# POWER.net
KiCad netlist of a schematic drawn in Altium Designer
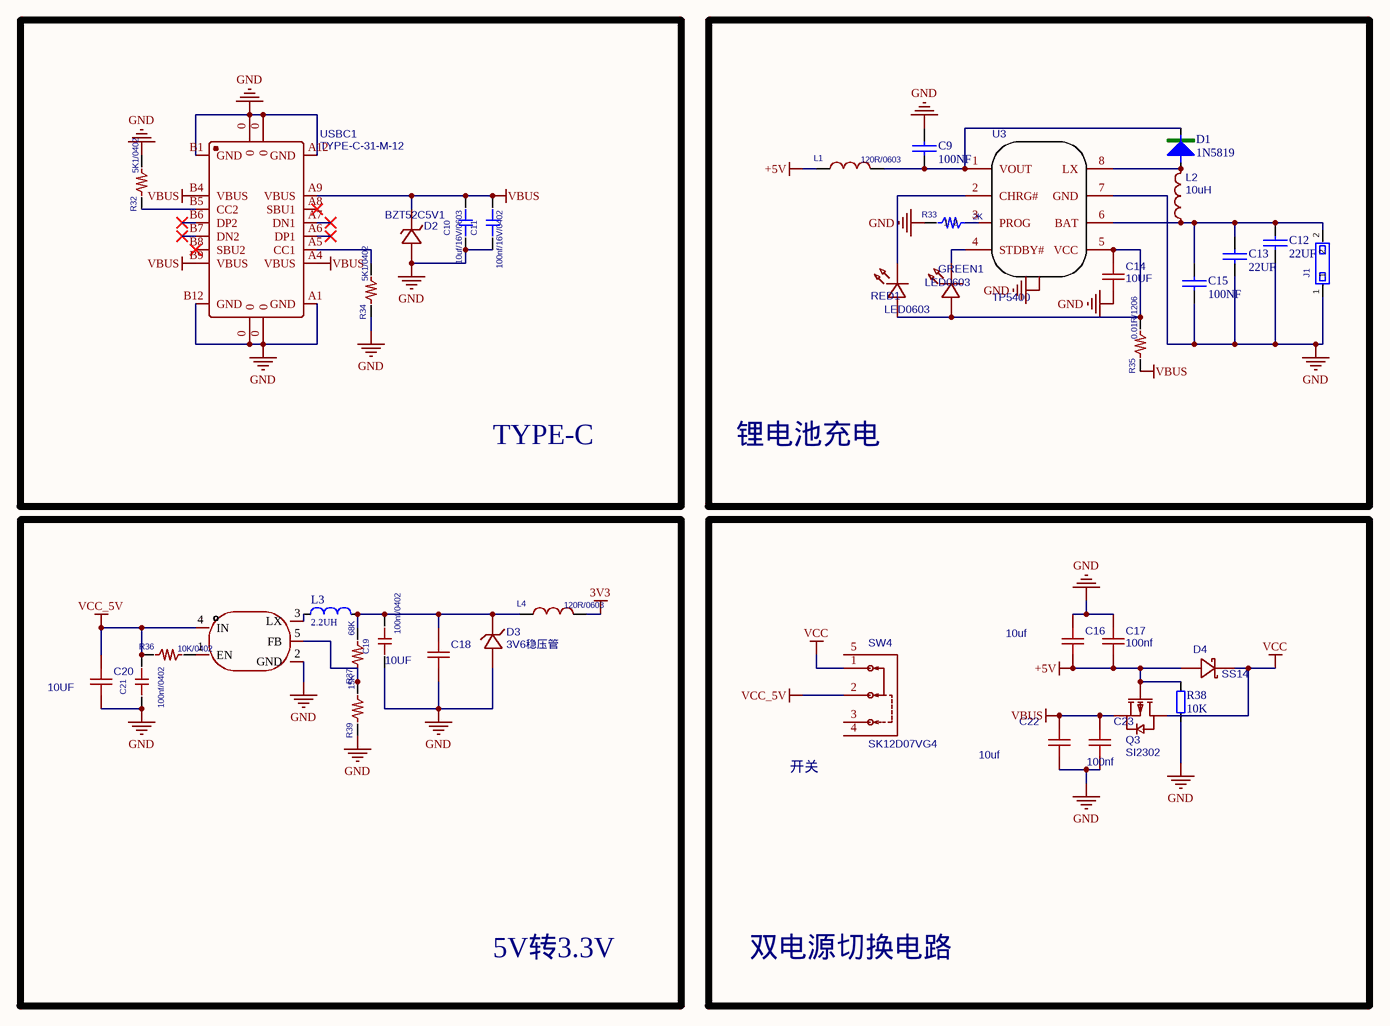
[diagram p0: POWER.SchDoc]

(export (version "E")
  (design (tool "Eeschema 10.0.6"))
  (components
    (comp (ref "C9")
      (value "100NF")
      (footprint "C0402")
      (description "Capacitor")
      (libsource (lib "mylib") (part "C0805"))
    )
    (comp (ref "C10")
      (value "10uf/16V/0603")
      (footprint "C0402")
      (fields (field (name "Comment") "100nf"))
      (libsource (lib "mylib") (part "C0402"))
    )
    (comp (ref "C11")
      (value "100nf/16V/0402")
      (footprint "C0402")
      (fields (field (name "Comment") "100nf"))
      (libsource (lib "mylib") (part "C0402"))
    )
    (comp (ref "C12")
      (value "22UF")
      (footprint "C0603")
      (description "Capacitor")
      (libsource (lib "mylib") (part "C0805"))
    )
    (comp (ref "C13")
      (value "22UF")
      (footprint "C0603")
      (description "Capacitor")
      (libsource (lib "mylib") (part "C0805"))
    )
    (comp (ref "C14")
      (value "10UF")
      (footprint "C0402")
      (fields
        (field (name "BOM_SUPPLIER PART") "C15415")
        (field (name "BOM_MANUFACTURER PART") "10uF")
        (field (name "CONTRIBUTOR") "LCSC")
      )
      (libsource (lib "mylib") (part "C0603"))
    )
    (comp (ref "C15")
      (value "100NF")
      (footprint "C0402")
      (description "Capacitor")
      (libsource (lib "mylib") (part "C0805"))
    )
    (comp (ref "C16")
      (value "10uf")
      (footprint "C0603")
      (fields
        (field (name "BOM_SUPPLIER PART") "C15415")
        (field (name "BOM_MANUFACTURER PART") "10uF")
        (field (name "CONTRIBUTOR") "LCSC")
      )
      (libsource (lib "Free Documents") (part "10uf"))
    )
    (comp (ref "C17")
      (value "100nf")
      (footprint "C0402")
      (fields
        (field (name "BOM_SUPPLIER PART") "C15415")
        (field (name "BOM_MANUFACTURER PART") "10uF")
        (field (name "CONTRIBUTOR") "LCSC")
      )
      (libsource (lib "Free Documents") (part "10uf"))
    )
    (comp (ref "C18")
      (value "10UF")
      (footprint "C0603")
      (fields
        (field (name "BOM_SUPPLIER PART") "C15415")
        (field (name "BOM_MANUFACTURER PART") "10uF")
        (field (name "CONTRIBUTOR") "LCSC")
      )
      (libsource (lib "mylib") (part "C0603"))
    )
    (comp (ref "C19")
      (value "100nf/0402")
      (footprint "C0402")
      (fields (field (name "Comment") "100nf"))
      (libsource (lib "mylib") (part "C0402"))
    )
    (comp (ref "C20")
      (value "10UF")
      (footprint "C0603")
      (fields
        (field (name "BOM_SUPPLIER PART") "C15415")
        (field (name "BOM_MANUFACTURER PART") "10uF")
        (field (name "CONTRIBUTOR") "LCSC")
      )
      (libsource (lib "mylib") (part "C0603"))
    )
    (comp (ref "C21")
      (value "100nf/0402")
      (footprint "C0402")
      (fields (field (name "Comment") "100nf"))
      (libsource (lib "mylib") (part "C0402"))
    )
    (comp (ref "C22")
      (value "10uf")
      (footprint "C0603")
      (fields
        (field (name "BOM_SUPPLIER PART") "C15415")
        (field (name "BOM_MANUFACTURER PART") "10uF")
        (field (name "CONTRIBUTOR") "LCSC")
      )
      (libsource (lib "Free Documents") (part "10uf"))
    )
    (comp (ref "C23")
      (value "100nf")
      (footprint "C0402")
      (fields
        (field (name "BOM_SUPPLIER PART") "C15415")
        (field (name "BOM_MANUFACTURER PART") "10uF")
        (field (name "CONTRIBUTOR") "LCSC")
      )
      (libsource (lib "Free Documents") (part "10uf"))
    )
    (comp (ref "D1")
      (value "1N5819")
      (footprint "SOD-123_L2.7-W1.6")
      (description "肖特基二极管")
      (libsource (lib "mylib") (part "1N5819"))
    )
    (comp (ref "D2")
      (value "BZT52C5V1")
      (footprint "SOD-123_L2.7-W1.6")
      (fields (field (name "BOM_SUPPLIER PART") "C1884555") (field (name "CONTRIBUTOR") "LCSC"))
      (libsource (lib "电源板") (part "BZT52C5V1_C1884555"))
    )
    (comp (ref "D3")
      (value "3V6稳压管")
      (footprint "SOD-123_L2.7-W1.6")
      (description "稳压管")
      (fields
        (field (name "BOM_SUPPLIER PART") "C216707")
        (field (name "BOM_MANUFACTURER PART") "BZT52C3V3")
        (field (name "CONTRIBUTOR") "LCSC")
      )
      (libsource (lib "mylib") (part "D_STB"))
    )
    (comp (ref "D4")
      (value "SS14")
      (footprint "SOD-123_L2.7-W1.6")
      (fields
        (field (name "BOM_SUPPLIER PART") "C2909963")
        (field (name "BOM_MANUFACTURER PART") "SS34")
        (field (name "CONTRIBUTOR") "LCSC")
      )
      (libsource (lib "mylib") (part "SS34_C2909963"))
    )
    (comp (ref "GREEN1")
      (value "LED0603")
      (footprint "LED0603")
      (fields
        (field (name "BOM_MANUFACTURER PART") "19-217/R6C-AL1M2VY/3T")
        (field (name "BOM_SUPPLIER PART") "C72044")
        (field (name "CONTRIBUTOR") "LCEDA_01")
      )
      (libsource (lib "mylib") (part "LED0603"))
    )
    (comp (ref "J1")
      (value "1X2PIN_SMD")
      (footprint "SMD1X2_2.54")
      (libsource (lib "mylib") (part "1X2PIN_SMD"))
    )
    (comp (ref "L1")
      (value "120R/0603")
      (footprint "L0603")
      (description "0603")
      (fields (field (name "Comment") "120R"))
      (libsource (lib "mylib") (part "FB0603"))
    )
    (comp (ref "L2")
      (value "10uH")
      (footprint "L_SMD_L4.0-W4.0")
      (fields
        (field (name "BOM_MANUFACTURER PART") "SWPA4030S100MT")
        (field (name "BOM_SUPPLIER PART") "C38117")
      )
      (libsource (lib "mylib") (part "10uH"))
    )
    (comp (ref "L3")
      (value "2.2UH")
      (footprint "L_SMD_L4.0-W4.0")
      (description "电感")
      (libsource (lib "mylib") (part "INDUCTOR"))
    )
    (comp (ref "L4")
      (value "120R/0603")
      (footprint "L0603")
      (description "0603")
      (fields (field (name "Comment") "120R"))
      (libsource (lib "mylib") (part "FB0603"))
    )
    (comp (ref "Q3")
      (value "SI2302")
      (footprint "SOT-23-3_L2.9-W1.6-P1.90")
      (description "P场效应管")
      (fields
        (field (name "BOM_SUPPLIER PART") "C518789")
        (field (name "BOM_MANUFACTURER PART") "FDN338P")
        (field (name "CONTRIBUTOR") "LCSC")
      )
      (libsource (lib "mylib") (part "FDN338P_C518789"))
    )
    (comp (ref "R32")
      (value "5K1/0402")
      (footprint "R0402")
      (fields (field (name "Comment") "5K1"))
      (libsource (lib "mylib") (part "R0402"))
    )
    (comp (ref "R33") (value "2K") (footprint "R0603") (libsource (lib "mylib") (part "R0603")))
    (comp (ref "R34")
      (value "5K1/0402")
      (footprint "R0402")
      (fields (field (name "Comment") "5K1"))
      (libsource (lib "mylib") (part "R0402"))
    )
    (comp (ref "R35")
      (value "0.01R/1206")
      (footprint "R1206")
      (fields (field (name "Comment") "0.01R"))
      (libsource (lib "mylib") (part "R1206"))
    )
    (comp (ref "R36")
      (value "10K/0402")
      (footprint "R0402")
      (fields (field (name "Comment") "R0603"))
      (libsource (lib "mylib") (part "R0402"))
    )
    (comp (ref "R37") (value "68K") (footprint "R0402") (libsource (lib "mylib") (part "R0402")))
    (comp (ref "R38") (value "10K") (footprint "R0402") (libsource (lib "") (part "R0402_1")))
    (comp (ref "R39") (value "15K") (footprint "R0402") (libsource (lib "mylib") (part "R0402")))
    (comp (ref "RED1")
      (value "LED0603")
      (footprint "LED0603")
      (fields
        (field (name "BOM_MANUFACTURER PART") "19-217/R6C-AL1M2VY/3T")
        (field (name "BOM_SUPPLIER PART") "C72044")
        (field (name "CONTRIBUTOR") "LCEDA_01")
      )
      (libsource (lib "mylib") (part "LED0603"))
    )
    (comp (ref "SW4")
      (value "SK12D07VG4")
      (footprint "SW-TH_5P")
      (description "拨动开关")
      (fields (field (name "BOM_SUPPLIER PART") "C393937") (field (name "CONTRIBUTOR") "LCSC"))
      (libsource (lib "mylib") (part "SW-bodong"))
    )
    (comp (ref "U3")
      (value "TP5400")
      (footprint "SOIC-8_L5.0-W4.0-P1.27-LS6.0_EP2.0")
      (description "锂电池充放电")
      (fields (field (name "BOM_SUPPLIER PART") "C24154"))
      (libsource (lib "mylib") (part "TP5400"))
    )
    (comp (ref "U4")
      (value "SY8088AAC")
      (footprint "SOT23-5")
      (fields (field (name "MANUFACTURER") "矽力杰silergy"))
      (libsource (lib "mylib") (part "SY8088AAC"))
    )
    (comp (ref "USBC1")
      (value "TYPE-C-31-M-12")
      (footprint "TYPEC_F_16_SMD_U")
      (fields (field (name "BOM_SUPPLIER PART") "C165948") (field (name "CONTRIBUTOR") "LCSC"))
      (libsource (lib "mylib") (part "TYPE-C-31-M-12"))
    )
  )
  (nets
    (net (code "1") (name "+5V") (class "Default")
      (node (ref "C16") (pin "2") (pinfunction "2_2") (pintype "passive"))
      (node (ref "C17") (pin "2") (pinfunction "2_2") (pintype "passive"))
      (node (ref "D4") (pin "2") (pinfunction "2_2") (pintype "passive"))
      (node (ref "L1") (pin "1") (pinfunction "1_1") (pintype "passive"))
      (node (ref "Q3") (pin "1") (pinfunction "G_1") (pintype "passive"))
      (node (ref "R38") (pin "2") (pinfunction "2_2") (pintype "passive"))
    )
    (net (code "2") (name "3V3") (class "Default")
      (node (ref "L4") (pin "2") (pinfunction "2_2") (pintype "passive"))
    )
    (net (code "3") (name "GND") (class "Default")
      (node (ref "C10") (pin "1") (pinfunction "1_1") (pintype "passive"))
      (node (ref "C11") (pin "1") (pinfunction "1_1") (pintype "passive"))
      (node (ref "C12") (pin "2") (pinfunction "2_2") (pintype "passive"))
      (node (ref "C13") (pin "2") (pinfunction "2_2") (pintype "passive"))
      (node (ref "C14") (pin "1") (pinfunction "1_1") (pintype "passive"))
      (node (ref "C15") (pin "2") (pinfunction "2_2") (pintype "passive"))
      (node (ref "C16") (pin "1") (pinfunction "1_1") (pintype "passive"))
      (node (ref "C17") (pin "1") (pinfunction "1_1") (pintype "passive"))
      (node (ref "C18") (pin "1") (pinfunction "1_1") (pintype "passive"))
      (node (ref "C19") (pin "1") (pinfunction "1_1") (pintype "passive"))
      (node (ref "C20") (pin "1") (pinfunction "1_1") (pintype "passive"))
      (node (ref "C21") (pin "1") (pinfunction "1_1") (pintype "passive"))
      (node (ref "C22") (pin "1") (pinfunction "1_1") (pintype "passive"))
      (node (ref "C23") (pin "1") (pinfunction "1_1") (pintype "passive"))
      (node (ref "C9") (pin "1") (pinfunction "1_1") (pintype "passive"))
      (node (ref "D2") (pin "2") (pinfunction "A_2") (pintype "passive"))
      (node (ref "D3") (pin "2") (pinfunction "2_2") (pintype "passive"))
      (node (ref "J1") (pin "1") (pinfunction "1_1") (pintype "passive"))
      (node (ref "R32") (pin "2") (pinfunction "2_2") (pintype "passive"))
      (node (ref "R33") (pin "1") (pinfunction "1_1") (pintype "passive"))
      (node (ref "R34") (pin "1") (pinfunction "1_1") (pintype "passive"))
      (node (ref "R38") (pin "1") (pinfunction "1_1") (pintype "passive"))
      (node (ref "R39") (pin "1") (pinfunction "1_1") (pintype "passive"))
      (node (ref "U3") (pin "7") (pinfunction "GND_7") (pintype "passive"))
      (node (ref "U3") (pin "9") (pinfunction "9_9") (pintype "passive"))
      (node (ref "U4") (pin "2") (pinfunction "GND_2") (pintype "passive"))
      (node (ref "USBC1") (pin "0") (pinfunction "0_0") (pintype "passive"))
      (node (ref "USBC1") (pin "A1") (pinfunction "GND_A1") (pintype "passive"))
      (node (ref "USBC1") (pin "A12") (pinfunction "GND_A12") (pintype "passive"))
      (node (ref "USBC1") (pin "B1") (pinfunction "GND_B1") (pintype "passive"))
      (node (ref "USBC1") (pin "B12") (pinfunction "GND_B12") (pintype "passive"))
    )
    (net (code "4") (name "Net-(C18-Pad2)") (class "Default")
      (node (ref "C18") (pin "2") (pinfunction "2_2") (pintype "passive"))
      (node (ref "C19") (pin "2") (pinfunction "2_2") (pintype "passive"))
      (node (ref "D3") (pin "1") (pinfunction "1_1") (pintype "passive"))
      (node (ref "L3") (pin "2") (pinfunction "2_2") (pintype "passive"))
      (node (ref "L4") (pin "1") (pinfunction "1_1") (pintype "passive"))
      (node (ref "R37") (pin "2") (pinfunction "2_2") (pintype "passive"))
    )
    (net (code "5") (name "Net-(U3-BAT)") (class "Default")
      (node (ref "C12") (pin "1") (pinfunction "1_1") (pintype "passive"))
      (node (ref "C13") (pin "1") (pinfunction "1_1") (pintype "passive"))
      (node (ref "C15") (pin "1") (pinfunction "1_1") (pintype "passive"))
      (node (ref "J1") (pin "2") (pinfunction "2_2") (pintype "passive"))
      (node (ref "L2") (pin "1") (pinfunction "1_1") (pintype "passive"))
      (node (ref "U3") (pin "6") (pinfunction "BAT_6") (pintype "passive"))
    )
    (net (code "6") (name "Net-(U3-CHRG#)") (class "Default")
      (node (ref "RED1") (pin "2") (pinfunction "2_2") (pintype "passive"))
      (node (ref "U3") (pin "2") (pinfunction "CHRG#_2") (pintype "passive"))
    )
    (net (code "7") (name "Net-(U3-LX)") (class "Default")
      (node (ref "D1") (pin "1") (pinfunction "1_1") (pintype "passive"))
      (node (ref "L2") (pin "2") (pinfunction "2_2") (pintype "passive"))
      (node (ref "U3") (pin "8") (pinfunction "LX_8") (pintype "passive"))
    )
    (net (code "8") (name "Net-(U3-PROG)") (class "Default")
      (node (ref "R33") (pin "2") (pinfunction "2_2") (pintype "passive"))
      (node (ref "U3") (pin "3") (pinfunction "PROG_3") (pintype "passive"))
    )
    (net (code "9") (name "Net-(U3-STDBY#)") (class "Default")
      (node (ref "GREEN1") (pin "2") (pinfunction "2_2") (pintype "passive"))
      (node (ref "U3") (pin "4") (pinfunction "STDBY#_4") (pintype "passive"))
    )
    (net (code "10") (name "Net-(U3-VCC)") (class "Default")
      (node (ref "C14") (pin "2") (pinfunction "2_2") (pintype "passive"))
      (node (ref "GREEN1") (pin "1") (pinfunction "1_1") (pintype "passive"))
      (node (ref "R35") (pin "2") (pinfunction "2_2") (pintype "passive"))
      (node (ref "RED1") (pin "1") (pinfunction "1_1") (pintype "passive"))
      (node (ref "U3") (pin "5") (pinfunction "VCC_5") (pintype "passive"))
    )
    (net (code "11") (name "Net-(U3-VOUT)") (class "Default")
      (node (ref "C9") (pin "2") (pinfunction "2_2") (pintype "passive"))
      (node (ref "D1") (pin "2") (pinfunction "2_2") (pintype "passive"))
      (node (ref "L1") (pin "2") (pinfunction "2_2") (pintype "passive"))
      (node (ref "U3") (pin "1") (pinfunction "VOUT_1") (pintype "passive"))
    )
    (net (code "12") (name "Net-(U4-EN)") (class "Default")
      (node (ref "R36") (pin "2") (pinfunction "2_2") (pintype "passive"))
      (node (ref "U4") (pin "1") (pinfunction "EN_1") (pintype "passive"))
    )
    (net (code "13") (name "Net-(U4-FB)") (class "Default")
      (node (ref "R37") (pin "1") (pinfunction "1_1") (pintype "passive"))
      (node (ref "R39") (pin "2") (pinfunction "2_2") (pintype "passive"))
      (node (ref "U4") (pin "5") (pinfunction "FB_5") (pintype "passive"))
    )
    (net (code "14") (name "Net-(U4-LX)") (class "Default")
      (node (ref "L3") (pin "1") (pinfunction "1_1") (pintype "passive"))
      (node (ref "U4") (pin "3") (pinfunction "LX_3") (pintype "passive"))
    )
    (net (code "15") (name "Net-(USBC1-CC1)") (class "Default")
      (node (ref "R34") (pin "2") (pinfunction "2_2") (pintype "passive"))
      (node (ref "USBC1") (pin "A5") (pinfunction "CC1_A5") (pintype "passive"))
    )
    (net (code "16") (name "Net-(USBC1-CC2)") (class "Default")
      (node (ref "R32") (pin "1") (pinfunction "1_1") (pintype "passive"))
      (node (ref "USBC1") (pin "B5") (pinfunction "CC2_B5") (pintype "passive"))
    )
    (net (code "17") (name "VBUS") (class "Default")
      (node (ref "C10") (pin "2") (pinfunction "2_2") (pintype "passive"))
      (node (ref "C11") (pin "2") (pinfunction "2_2") (pintype "passive"))
      (node (ref "C22") (pin "2") (pinfunction "2_2") (pintype "passive"))
      (node (ref "C23") (pin "2") (pinfunction "2_2") (pintype "passive"))
      (node (ref "D2") (pin "1") (pinfunction "K_1") (pintype "passive"))
      (node (ref "Q3") (pin "2") (pinfunction "S_2") (pintype "passive"))
      (node (ref "R35") (pin "1") (pinfunction "1_1") (pintype "passive"))
      (node (ref "USBC1") (pin "A4") (pinfunction "VBUS_A4") (pintype "passive"))
      (node (ref "USBC1") (pin "A9") (pinfunction "VBUS_A9") (pintype "passive"))
      (node (ref "USBC1") (pin "B4") (pinfunction "VBUS_B4") (pintype "passive"))
      (node (ref "USBC1") (pin "B9") (pinfunction "VBUS_B9") (pintype "passive"))
    )
    (net (code "18") (name "VCC") (class "Default")
      (node (ref "D4") (pin "1") (pinfunction "1_1") (pintype "passive"))
      (node (ref "Q3") (pin "3") (pinfunction "D_3") (pintype "passive"))
      (node (ref "SW4") (pin "1") (pinfunction "1_1") (pintype "passive"))
    )
    (net (code "19") (name "VCC_5V") (class "Default")
      (node (ref "C20") (pin "2") (pinfunction "2_2") (pintype "passive"))
      (node (ref "C21") (pin "2") (pinfunction "2_2") (pintype "passive"))
      (node (ref "R36") (pin "1") (pinfunction "1_1") (pintype "passive"))
      (node (ref "SW4") (pin "2") (pinfunction "2_2") (pintype "passive"))
      (node (ref "U4") (pin "4") (pinfunction "IN_4") (pintype "passive"))
    )
    (net (code "20") (name "unconnected-(SW4-Pad3)") (class "Default")
      (node (ref "SW4") (pin "3") (pinfunction "3_3") (pintype "passive"))
    )
    (net (code "21") (name "unconnected-(SW4-Pad4)") (class "Default")
      (node (ref "SW4") (pin "4") (pinfunction "4_4") (pintype "passive"))
    )
    (net (code "22") (name "unconnected-(SW4-Pad5)") (class "Default")
      (node (ref "SW4") (pin "5") (pinfunction "5_5") (pintype "passive"))
    )
    (net (code "23") (name "unconnected-(USBC1-DN1-PadA7)") (class "Default")
      (node (ref "USBC1") (pin "A7") (pinfunction "DN1_A7") (pintype "passive+no_connect"))
    )
    (net (code "24") (name "unconnected-(USBC1-DN2-PadB7)") (class "Default")
      (node (ref "USBC1") (pin "B7") (pinfunction "DN2_B7") (pintype "passive+no_connect"))
    )
    (net (code "25") (name "unconnected-(USBC1-DP1-PadA6)") (class "Default")
      (node (ref "USBC1") (pin "A6") (pinfunction "DP1_A6") (pintype "passive+no_connect"))
    )
    (net (code "26") (name "unconnected-(USBC1-DP2-PadB6)") (class "Default")
      (node (ref "USBC1") (pin "B6") (pinfunction "DP2_B6") (pintype "passive+no_connect"))
    )
    (net (code "27") (name "unconnected-(USBC1-SBU1-PadA8)") (class "Default")
      (node (ref "USBC1") (pin "A8") (pinfunction "SBU1_A8") (pintype "passive+no_connect"))
    )
    (net (code "28") (name "unconnected-(USBC1-SBU2-PadB8)") (class "Default")
      (node (ref "USBC1") (pin "B8") (pinfunction "SBU2_B8") (pintype "passive+no_connect"))
    )
  )
)
